# mainboard.net
KiCad netlist of a schematic drawn in EAGLE
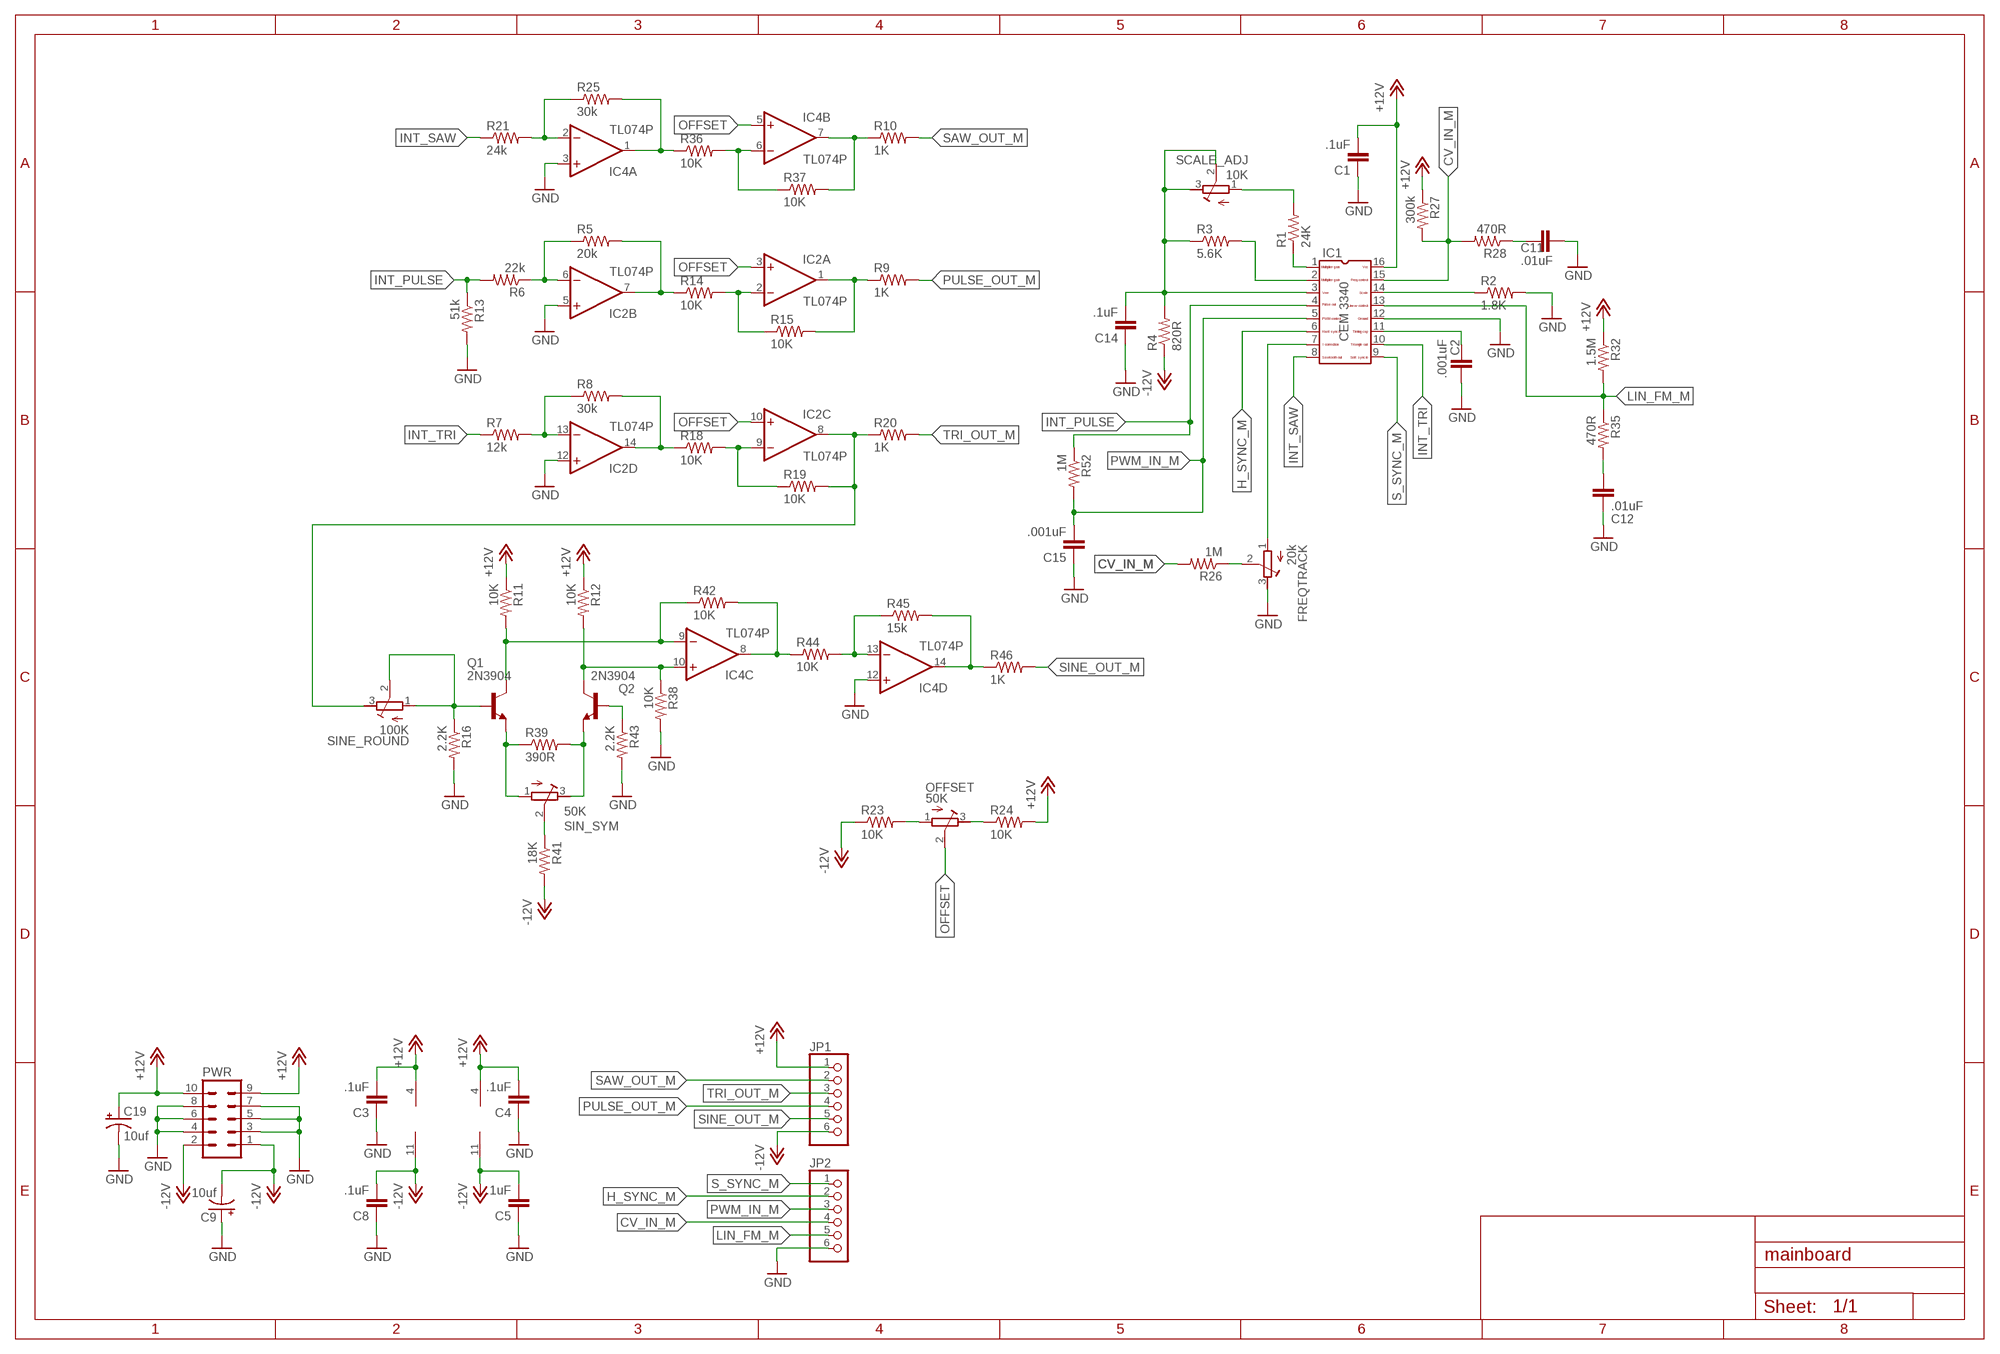
[diagram p0: schematic, sheet 1]

(export (version "E")
  (design (tool "Eeschema 10.0.6"))
  (components
    (comp (ref "C1")
      (value ".1uF")
      (footprint "eagle-import:C050-024X044")
      (libsource (lib "eagle-import") (part "resistor_C-EU050-024X044"))
    )
    (comp (ref "C2")
      (value ".001uF")
      (footprint "eagle-import:C150-054X183")
      (libsource (lib "eagle-import") (part "C-EU150-054X183"))
    )
    (comp (ref "C3")
      (value ".1uF")
      (footprint "eagle-import:C050-024X044")
      (libsource (lib "eagle-import") (part "resistor_C-EU050-024X044"))
    )
    (comp (ref "C4")
      (value ".1uF")
      (footprint "eagle-import:C050-024X044")
      (libsource (lib "eagle-import") (part "resistor_C-EU050-024X044"))
    )
    (comp (ref "C5")
      (value ".1uF")
      (footprint "eagle-import:C050-024X044")
      (libsource (lib "eagle-import") (part "resistor_C-EU050-024X044"))
    )
    (comp (ref "C8")
      (value ".1uF")
      (footprint "eagle-import:C050-024X044")
      (libsource (lib "eagle-import") (part "resistor_C-EU050-024X044"))
    )
    (comp (ref "C9")
      (value "10uf")
      (footprint "eagle-import:E2,5-5")
      (libsource (lib "eagle-import") (part "CPOL-USE2.5-5"))
    )
    (comp (ref "C11")
      (value ".01uF")
      (footprint "eagle-import:C050-024X044")
      (libsource (lib "eagle-import") (part "resistor_C-EU050-024X044"))
    )
    (comp (ref "C12")
      (value ".01uF")
      (footprint "eagle-import:C050-024X044")
      (libsource (lib "eagle-import") (part "resistor_C-EU050-024X044"))
    )
    (comp (ref "C14")
      (value ".1uF")
      (footprint "eagle-import:C050-024X044")
      (libsource (lib "eagle-import") (part "resistor_C-EU050-024X044"))
    )
    (comp (ref "C15")
      (value ".001uF")
      (footprint "eagle-import:C050-024X044")
      (libsource (lib "eagle-import") (part "resistor_C-EU050-024X044"))
    )
    (comp (ref "C19")
      (value "10uf")
      (footprint "eagle-import:E2,5-5")
      (libsource (lib "eagle-import") (part "CPOL-USE2.5-5"))
    )
    (comp (ref "FREQTRACK")
      (value "20k")
      (footprint "eagle-import:RTRIM3296W")
      (libsource (lib "eagle-import") (part "R-TRIMM3296W"))
    )
    (comp (ref "IC1")
      (value "CEM3340")
      (footprint "eagle-import:DIL16")
      (libsource (lib "eagle-import") (part "CEM3340"))
    )
    (comp (ref "IC2")
      (value "TL074P")
      (footprint "eagle-import:DIL14")
      (libsource (lib "eagle-import") (part "TL074P"))
    )
    (comp (ref "IC4")
      (value "TL074P")
      (footprint "eagle-import:DIL14")
      (libsource (lib "eagle-import") (part "linear_262_TL074P"))
    )
    (comp (ref "JP1")
      (value "PINHD-1X6")
      (footprint "eagle-import:1X06")
      (libsource (lib "eagle-import") (part "PINHD-1X6"))
    )
    (comp (ref "JP2")
      (value "PINHD-1X6")
      (footprint "eagle-import:1X06")
      (libsource (lib "eagle-import") (part "PINHD-1X6"))
    )
    (comp (ref "OFFSET")
      (value "50K")
      (footprint "eagle-import:RTRIM3296W")
      (libsource (lib "eagle-import") (part "R-TRIMM3296W"))
    )
    (comp (ref "PWR")
      (value "ML10")
      (footprint "eagle-import:ML10")
      (libsource (lib "eagle-import") (part "ML10"))
    )
    (comp (ref "Q1")
      (value "2N3904")
      (footprint "eagle-import:TO92")
      (libsource (lib "eagle-import") (part "2N3904"))
    )
    (comp (ref "Q2")
      (value "2N3904")
      (footprint "eagle-import:TO92")
      (libsource (lib "eagle-import") (part "2N3904"))
    )
    (comp (ref "R1")
      (value "24K")
      (footprint "eagle-import:0207_7")
      (libsource (lib "eagle-import") (part "R-US_0207/7"))
    )
    (comp (ref "R2")
      (value "1.8K")
      (footprint "eagle-import:0207_7")
      (libsource (lib "eagle-import") (part "R-US_0207/7"))
    )
    (comp (ref "R3")
      (value "5.6K")
      (footprint "eagle-import:0207_7")
      (libsource (lib "eagle-import") (part "R-US_0207/7"))
    )
    (comp (ref "R4")
      (value "820R")
      (footprint "eagle-import:0207_7")
      (libsource (lib "eagle-import") (part "R-US_0207/7"))
    )
    (comp (ref "R5")
      (value "20k")
      (footprint "eagle-import:0207_7")
      (libsource (lib "eagle-import") (part "R-US_0207/7"))
    )
    (comp (ref "R6")
      (value "22k")
      (footprint "eagle-import:0207_7")
      (libsource (lib "eagle-import") (part "R-US_0207/7"))
    )
    (comp (ref "R7")
      (value "12k")
      (footprint "eagle-import:0207_7")
      (libsource (lib "eagle-import") (part "R-US_0207/7"))
    )
    (comp (ref "R8")
      (value "30k")
      (footprint "eagle-import:0207_7")
      (libsource (lib "eagle-import") (part "R-US_0207/7"))
    )
    (comp (ref "R9")
      (value "1K")
      (footprint "eagle-import:0207_7")
      (libsource (lib "eagle-import") (part "R-US_0207/7"))
    )
    (comp (ref "R10")
      (value "1K")
      (footprint "eagle-import:0207_7")
      (libsource (lib "eagle-import") (part "R-US_0207/7"))
    )
    (comp (ref "R11")
      (value "10K")
      (footprint "eagle-import:0207_7")
      (libsource (lib "eagle-import") (part "R-US_0207/7"))
    )
    (comp (ref "R12")
      (value "10K")
      (footprint "eagle-import:0207_7")
      (libsource (lib "eagle-import") (part "R-US_0207/7"))
    )
    (comp (ref "R13")
      (value "51k")
      (footprint "eagle-import:0207_7")
      (libsource (lib "eagle-import") (part "R-US_0207/7"))
    )
    (comp (ref "R14")
      (value "10K")
      (footprint "eagle-import:0207_7")
      (libsource (lib "eagle-import") (part "R-US_0207/7"))
    )
    (comp (ref "R15")
      (value "10K")
      (footprint "eagle-import:0207_7")
      (libsource (lib "eagle-import") (part "R-US_0207/7"))
    )
    (comp (ref "R16")
      (value "2.2K")
      (footprint "eagle-import:0207_7")
      (libsource (lib "eagle-import") (part "R-US_0207/7"))
    )
    (comp (ref "R18")
      (value "10K")
      (footprint "eagle-import:0207_7")
      (libsource (lib "eagle-import") (part "R-US_0207/7"))
    )
    (comp (ref "R19")
      (value "10K")
      (footprint "eagle-import:0207_7")
      (libsource (lib "eagle-import") (part "R-US_0207/7"))
    )
    (comp (ref "R20")
      (value "1K")
      (footprint "eagle-import:0207_7")
      (libsource (lib "eagle-import") (part "R-US_0207/7"))
    )
    (comp (ref "R21")
      (value "24k")
      (footprint "eagle-import:0207_7")
      (libsource (lib "eagle-import") (part "R-US_0207/7"))
    )
    (comp (ref "R23")
      (value "10K")
      (footprint "eagle-import:0207_7")
      (libsource (lib "eagle-import") (part "R-US_0207/7"))
    )
    (comp (ref "R24")
      (value "10K")
      (footprint "eagle-import:0207_7")
      (libsource (lib "eagle-import") (part "resistor_348_R-US_0207/7"))
    )
    (comp (ref "R25")
      (value "30k")
      (footprint "eagle-import:0207_7")
      (libsource (lib "eagle-import") (part "R-US_0207/7"))
    )
    (comp (ref "R26")
      (value "1M")
      (footprint "eagle-import:0207_7")
      (libsource (lib "eagle-import") (part "R-US_0207/7"))
    )
    (comp (ref "R27")
      (value "300k")
      (footprint "eagle-import:0207_7")
      (libsource (lib "eagle-import") (part "R-US_0207/7"))
    )
    (comp (ref "R28")
      (value "470R")
      (footprint "eagle-import:0207_7")
      (libsource (lib "eagle-import") (part "R-US_0207/7"))
    )
    (comp (ref "R32")
      (value "1.5M")
      (footprint "eagle-import:0207_7")
      (libsource (lib "eagle-import") (part "R-US_0207/7"))
    )
    (comp (ref "R35")
      (value "470R")
      (footprint "eagle-import:0207_7")
      (libsource (lib "eagle-import") (part "R-US_0207/7"))
    )
    (comp (ref "R36")
      (value "10K")
      (footprint "eagle-import:0207_7")
      (libsource (lib "eagle-import") (part "R-US_0207/7"))
    )
    (comp (ref "R37")
      (value "10K")
      (footprint "eagle-import:0207_7")
      (libsource (lib "eagle-import") (part "R-US_0207/7"))
    )
    (comp (ref "R38")
      (value "10K")
      (footprint "eagle-import:0207_7")
      (libsource (lib "eagle-import") (part "R-US_0207/7"))
    )
    (comp (ref "R39")
      (value "390R")
      (footprint "eagle-import:0207_7")
      (libsource (lib "eagle-import") (part "R-US_0207/7"))
    )
    (comp (ref "R41")
      (value "18K")
      (footprint "eagle-import:0207_7")
      (libsource (lib "eagle-import") (part "R-US_0207/7"))
    )
    (comp (ref "R42")
      (value "10K")
      (footprint "eagle-import:0207_7")
      (libsource (lib "eagle-import") (part "R-US_0207/7"))
    )
    (comp (ref "R43")
      (value "2.2K")
      (footprint "eagle-import:0207_7")
      (libsource (lib "eagle-import") (part "R-US_0207/7"))
    )
    (comp (ref "R44")
      (value "10K")
      (footprint "eagle-import:0207_7")
      (libsource (lib "eagle-import") (part "R-US_0207/7"))
    )
    (comp (ref "R45")
      (value "15k")
      (footprint "eagle-import:0207_7")
      (libsource (lib "eagle-import") (part "R-US_0207/7"))
    )
    (comp (ref "R46")
      (value "1K")
      (footprint "eagle-import:0207_7")
      (libsource (lib "eagle-import") (part "R-US_0207/7"))
    )
    (comp (ref "R52")
      (value "1M")
      (footprint "eagle-import:0207_7")
      (libsource (lib "eagle-import") (part "R-US_0207/7"))
    )
    (comp (ref "SCALE_ADJ")
      (value "10K")
      (footprint "eagle-import:RTRIM3296W")
      (libsource (lib "eagle-import") (part "R-TRIMM3296W"))
    )
    (comp (ref "SINE_ROUND")
      (value "100K")
      (footprint "eagle-import:RTRIM3296W")
      (libsource (lib "eagle-import") (part "R-TRIMM3296W"))
    )
    (comp (ref "SIN_SYM")
      (value "50K")
      (footprint "eagle-import:RTRIM3296W")
      (libsource (lib "eagle-import") (part "R-TRIMM3296W"))
    )
  )
  (nets
    (net (code "1") (name "+12V") (class "Default")
      (node (ref "C1") (pin "2") (pinfunction "2_2") (pintype "passive"))
      (node (ref "C19") (pin "+") (pinfunction "+_+") (pintype "passive"))
      (node (ref "C3") (pin "2") (pinfunction "2_2") (pintype "passive"))
      (node (ref "C4") (pin "2") (pinfunction "2_2") (pintype "passive"))
      (node (ref "IC1") (pin "16") (pinfunction "16_16") (pintype "power_in"))
      (node (ref "IC2") (pin "4") (pinfunction "V+_4") (pintype "power_in"))
      (node (ref "IC4") (pin "4") (pinfunction "V+_4") (pintype "power_in"))
      (node (ref "JP1") (pin "1") (pinfunction "1_1") (pintype "passive"))
      (node (ref "PWR") (pin "10") (pinfunction "10_10") (pintype "passive"))
      (node (ref "PWR") (pin "9") (pinfunction "9_9") (pintype "passive"))
      (node (ref "R11") (pin "1") (pinfunction "1_1") (pintype "passive"))
      (node (ref "R12") (pin "1") (pinfunction "1_1") (pintype "passive"))
      (node (ref "R24") (pin "2") (pinfunction "2_2") (pintype "passive"))
      (node (ref "R27") (pin "1") (pinfunction "1_1") (pintype "passive"))
      (node (ref "R32") (pin "1") (pinfunction "1_1") (pintype "passive"))
    )
    (net (code "2") (name "-12V") (class "Default")
      (node (ref "C5") (pin "2") (pinfunction "2_2") (pintype "passive"))
      (node (ref "C8") (pin "2") (pinfunction "2_2") (pintype "passive"))
      (node (ref "C9") (pin "-") (pinfunction "-_-") (pintype "passive"))
      (node (ref "IC2") (pin "11") (pinfunction "V-_11") (pintype "power_in"))
      (node (ref "IC4") (pin "11") (pinfunction "V-_11") (pintype "power_in"))
      (node (ref "JP1") (pin "6") (pinfunction "6_6") (pintype "passive"))
      (node (ref "PWR") (pin "1") (pinfunction "1_1") (pintype "passive"))
      (node (ref "PWR") (pin "2") (pinfunction "2_2") (pintype "passive"))
      (node (ref "R23") (pin "1") (pinfunction "1_1") (pintype "passive"))
      (node (ref "R4") (pin "1") (pinfunction "1_1") (pintype "passive"))
      (node (ref "R41") (pin "2") (pinfunction "2_2") (pintype "passive"))
    )
    (net (code "3") (name "CV_IN_M") (class "Default")
      (node (ref "IC1") (pin "15") (pinfunction "15_15") (pintype "input"))
      (node (ref "JP2") (pin "4") (pinfunction "4_4") (pintype "passive"))
      (node (ref "R26") (pin "2") (pinfunction "2_2") (pintype "passive"))
      (node (ref "R27") (pin "2") (pinfunction "2_2") (pintype "passive"))
      (node (ref "R28") (pin "2") (pinfunction "2_2") (pintype "passive"))
    )
    (net (code "4") (name "GND") (class "Default")
      (node (ref "C1") (pin "1") (pinfunction "1_1") (pintype "passive"))
      (node (ref "C11") (pin "1") (pinfunction "1_1") (pintype "passive"))
      (node (ref "C12") (pin "2") (pinfunction "2_2") (pintype "passive"))
      (node (ref "C14") (pin "1") (pinfunction "1_1") (pintype "passive"))
      (node (ref "C15") (pin "1") (pinfunction "1_1") (pintype "passive"))
      (node (ref "C19") (pin "-") (pinfunction "-_-") (pintype "passive"))
      (node (ref "C2") (pin "2") (pinfunction "2_2") (pintype "passive"))
      (node (ref "C3") (pin "1") (pinfunction "1_1") (pintype "passive"))
      (node (ref "C4") (pin "1") (pinfunction "1_1") (pintype "passive"))
      (node (ref "C5") (pin "1") (pinfunction "1_1") (pintype "passive"))
      (node (ref "C8") (pin "1") (pinfunction "1_1") (pintype "passive"))
      (node (ref "C9") (pin "+") (pinfunction "+_+") (pintype "passive"))
      (node (ref "FREQTRACK") (pin "3") (pinfunction "E_3") (pintype "passive"))
      (node (ref "IC1") (pin "12") (pinfunction "12_12") (pintype "power_in"))
      (node (ref "IC2") (pin "12") (pinfunction "+IN_12") (pintype "input"))
      (node (ref "IC2") (pin "5") (pinfunction "+IN_5") (pintype "input"))
      (node (ref "IC4") (pin "12") (pinfunction "+IN_12") (pintype "input"))
      (node (ref "IC4") (pin "3") (pinfunction "+IN_3") (pintype "input"))
      (node (ref "JP2") (pin "6") (pinfunction "6_6") (pintype "passive"))
      (node (ref "PWR") (pin "3") (pinfunction "3_3") (pintype "passive"))
      (node (ref "PWR") (pin "4") (pinfunction "4_4") (pintype "passive"))
      (node (ref "PWR") (pin "5") (pinfunction "5_5") (pintype "passive"))
      (node (ref "PWR") (pin "6") (pinfunction "6_6") (pintype "passive"))
      (node (ref "PWR") (pin "7") (pinfunction "7_7") (pintype "passive"))
      (node (ref "PWR") (pin "8") (pinfunction "8_8") (pintype "passive"))
      (node (ref "R13") (pin "2") (pinfunction "2_2") (pintype "passive"))
      (node (ref "R16") (pin "2") (pinfunction "2_2") (pintype "passive"))
      (node (ref "R2") (pin "2") (pinfunction "2_2") (pintype "passive"))
      (node (ref "R38") (pin "2") (pinfunction "2_2") (pintype "passive"))
      (node (ref "R43") (pin "2") (pinfunction "2_2") (pintype "passive"))
    )
    (net (code "5") (name "H_SYNC_M") (class "Default")
      (node (ref "IC1") (pin "6") (pinfunction "6_6") (pintype "input"))
      (node (ref "JP2") (pin "2") (pinfunction "2_2") (pintype "passive"))
    )
    (net (code "6") (name "INT_PULSE") (class "Default")
      (node (ref "IC1") (pin "4") (pinfunction "4_4") (pintype "output"))
      (node (ref "R13") (pin "1") (pinfunction "1_1") (pintype "passive"))
      (node (ref "R52") (pin "1") (pinfunction "1_1") (pintype "passive"))
      (node (ref "R6") (pin "2") (pinfunction "2_2") (pintype "passive"))
    )
    (net (code "7") (name "INT_SAW") (class "Default")
      (node (ref "IC1") (pin "8") (pinfunction "8_8") (pintype "output"))
      (node (ref "R21") (pin "1") (pinfunction "1_1") (pintype "passive"))
    )
    (net (code "8") (name "INT_TRI") (class "Default")
      (node (ref "IC1") (pin "10") (pinfunction "10_10") (pintype "output"))
      (node (ref "R7") (pin "1") (pinfunction "1_1") (pintype "passive"))
    )
    (net (code "9") (name "LIN_FM_M") (class "Default")
      (node (ref "IC1") (pin "13") (pinfunction "13_13") (pintype "input"))
      (node (ref "JP2") (pin "5") (pinfunction "5_5") (pintype "passive"))
      (node (ref "R32") (pin "2") (pinfunction "2_2") (pintype "passive"))
      (node (ref "R35") (pin "1") (pinfunction "1_1") (pintype "passive"))
    )
    (net (code "10") (name "Net-(C2-Pad1)") (class "Default")
      (node (ref "C2") (pin "1") (pinfunction "1_1") (pintype "passive"))
      (node (ref "IC1") (pin "11") (pinfunction "11_11") (pintype "bidirectional"))
    )
    (net (code "11") (name "Net-(C11-Pad2)") (class "Default")
      (node (ref "C11") (pin "2") (pinfunction "2_2") (pintype "passive"))
      (node (ref "R28") (pin "1") (pinfunction "1_1") (pintype "passive"))
    )
    (net (code "12") (name "Net-(C12-Pad1)") (class "Default")
      (node (ref "C12") (pin "1") (pinfunction "1_1") (pintype "passive"))
      (node (ref "R35") (pin "2") (pinfunction "2_2") (pintype "passive"))
    )
    (net (code "13") (name "Net-(FREQTRACK-A)") (class "Default")
      (node (ref "FREQTRACK") (pin "1") (pinfunction "A_1") (pintype "passive"))
      (node (ref "IC1") (pin "7") (pinfunction "7_7") (pintype "bidirectional"))
    )
    (net (code "14") (name "Net-(FREQTRACK-S)") (class "Default")
      (node (ref "FREQTRACK") (pin "2") (pinfunction "S_2") (pintype "passive"))
      (node (ref "R26") (pin "1") (pinfunction "1_1") (pintype "passive"))
    )
    (net (code "15") (name "Net-(IC1-Pad1)") (class "Default")
      (node (ref "IC1") (pin "1") (pinfunction "1_1") (pintype "bidirectional"))
      (node (ref "R1") (pin "1") (pinfunction "1_1") (pintype "passive"))
    )
    (net (code "16") (name "Net-(IC1-Pad2)") (class "Default")
      (node (ref "IC1") (pin "2") (pinfunction "2_2") (pintype "bidirectional"))
      (node (ref "R3") (pin "2") (pinfunction "2_2") (pintype "passive"))
    )
    (net (code "17") (name "Net-(IC1-Pad14)") (class "Default")
      (node (ref "IC1") (pin "14") (pinfunction "14_14") (pintype "input"))
      (node (ref "R2") (pin "1") (pinfunction "1_1") (pintype "passive"))
    )
    (net (code "18") (name "Net-(IC2A--IN)") (class "Default")
      (node (ref "IC2") (pin "2") (pinfunction "-IN_2") (pintype "input"))
      (node (ref "R14") (pin "2") (pinfunction "2_2") (pintype "passive"))
      (node (ref "R15") (pin "1") (pinfunction "1_1") (pintype "passive"))
    )
    (net (code "19") (name "Net-(IC2A-OUT)") (class "Default")
      (node (ref "IC2") (pin "1") (pinfunction "OUT_1") (pintype "output"))
      (node (ref "R15") (pin "2") (pinfunction "2_2") (pintype "passive"))
      (node (ref "R9") (pin "1") (pinfunction "1_1") (pintype "passive"))
    )
    (net (code "20") (name "Net-(IC2B--IN)") (class "Default")
      (node (ref "IC2") (pin "6") (pinfunction "-IN_6") (pintype "input"))
      (node (ref "R5") (pin "1") (pinfunction "1_1") (pintype "passive"))
      (node (ref "R6") (pin "1") (pinfunction "1_1") (pintype "passive"))
    )
    (net (code "21") (name "Net-(IC2B-OUT)") (class "Default")
      (node (ref "IC2") (pin "7") (pinfunction "OUT_7") (pintype "output"))
      (node (ref "R14") (pin "1") (pinfunction "1_1") (pintype "passive"))
      (node (ref "R5") (pin "2") (pinfunction "2_2") (pintype "passive"))
    )
    (net (code "22") (name "Net-(IC2C--IN)") (class "Default")
      (node (ref "IC2") (pin "9") (pinfunction "-IN_9") (pintype "input"))
      (node (ref "R18") (pin "2") (pinfunction "2_2") (pintype "passive"))
      (node (ref "R19") (pin "1") (pinfunction "1_1") (pintype "passive"))
    )
    (net (code "23") (name "Net-(IC2C-OUT)") (class "Default")
      (node (ref "IC2") (pin "8") (pinfunction "OUT_8") (pintype "output"))
      (node (ref "R19") (pin "2") (pinfunction "2_2") (pintype "passive"))
      (node (ref "R20") (pin "1") (pinfunction "1_1") (pintype "passive"))
      (node (ref "SINE_ROUND") (pin "3") (pinfunction "E_3") (pintype "passive"))
    )
    (net (code "24") (name "Net-(IC2D--IN)") (class "Default")
      (node (ref "IC2") (pin "13") (pinfunction "-IN_13") (pintype "input"))
      (node (ref "R7") (pin "2") (pinfunction "2_2") (pintype "passive"))
      (node (ref "R8") (pin "1") (pinfunction "1_1") (pintype "passive"))
    )
    (net (code "25") (name "Net-(IC2D-OUT)") (class "Default")
      (node (ref "IC2") (pin "14") (pinfunction "OUT_14") (pintype "output"))
      (node (ref "R18") (pin "1") (pinfunction "1_1") (pintype "passive"))
      (node (ref "R8") (pin "2") (pinfunction "2_2") (pintype "passive"))
    )
    (net (code "26") (name "Net-(IC4A--IN)") (class "Default")
      (node (ref "IC4") (pin "2") (pinfunction "-IN_2") (pintype "input"))
      (node (ref "R21") (pin "2") (pinfunction "2_2") (pintype "passive"))
      (node (ref "R25") (pin "1") (pinfunction "1_1") (pintype "passive"))
    )
    (net (code "27") (name "Net-(IC4A-OUT)") (class "Default")
      (node (ref "IC4") (pin "1") (pinfunction "OUT_1") (pintype "output"))
      (node (ref "R25") (pin "2") (pinfunction "2_2") (pintype "passive"))
      (node (ref "R36") (pin "1") (pinfunction "1_1") (pintype "passive"))
    )
    (net (code "28") (name "Net-(IC4B--IN)") (class "Default")
      (node (ref "IC4") (pin "6") (pinfunction "-IN_6") (pintype "input"))
      (node (ref "R36") (pin "2") (pinfunction "2_2") (pintype "passive"))
      (node (ref "R37") (pin "1") (pinfunction "1_1") (pintype "passive"))
    )
    (net (code "29") (name "Net-(IC4B-OUT)") (class "Default")
      (node (ref "IC4") (pin "7") (pinfunction "OUT_7") (pintype "output"))
      (node (ref "R10") (pin "1") (pinfunction "1_1") (pintype "passive"))
      (node (ref "R37") (pin "2") (pinfunction "2_2") (pintype "passive"))
    )
    (net (code "30") (name "Net-(IC4C-+IN)") (class "Default")
      (node (ref "IC4") (pin "10") (pinfunction "+IN_10") (pintype "input"))
      (node (ref "Q2") (pin "1") (pinfunction "C_1") (pintype "passive"))
      (node (ref "R12") (pin "2") (pinfunction "2_2") (pintype "passive"))
      (node (ref "R38") (pin "1") (pinfunction "1_1") (pintype "passive"))
    )
    (net (code "31") (name "Net-(IC4C--IN)") (class "Default")
      (node (ref "IC4") (pin "9") (pinfunction "-IN_9") (pintype "input"))
      (node (ref "Q1") (pin "1") (pinfunction "C_1") (pintype "passive"))
      (node (ref "R11") (pin "2") (pinfunction "2_2") (pintype "passive"))
      (node (ref "R42") (pin "1") (pinfunction "1_1") (pintype "passive"))
    )
    (net (code "32") (name "Net-(IC4C-OUT)") (class "Default")
      (node (ref "IC4") (pin "8") (pinfunction "OUT_8") (pintype "output"))
      (node (ref "R42") (pin "2") (pinfunction "2_2") (pintype "passive"))
      (node (ref "R44") (pin "1") (pinfunction "1_1") (pintype "passive"))
    )
    (net (code "33") (name "Net-(IC4D--IN)") (class "Default")
      (node (ref "IC4") (pin "13") (pinfunction "-IN_13") (pintype "input"))
      (node (ref "R44") (pin "2") (pinfunction "2_2") (pintype "passive"))
      (node (ref "R45") (pin "1") (pinfunction "1_1") (pintype "passive"))
    )
    (net (code "34") (name "Net-(IC4D-OUT)") (class "Default")
      (node (ref "IC4") (pin "14") (pinfunction "OUT_14") (pintype "output"))
      (node (ref "R45") (pin "2") (pinfunction "2_2") (pintype "passive"))
      (node (ref "R46") (pin "1") (pinfunction "1_1") (pintype "passive"))
    )
    (net (code "35") (name "Net-(OFFSET-A)") (class "Default")
      (node (ref "OFFSET") (pin "1") (pinfunction "A_1") (pintype "passive"))
      (node (ref "R23") (pin "2") (pinfunction "2_2") (pintype "passive"))
    )
    (net (code "36") (name "Net-(OFFSET-E)") (class "Default")
      (node (ref "OFFSET") (pin "3") (pinfunction "E_3") (pintype "passive"))
      (node (ref "R24") (pin "1") (pinfunction "1_1") (pintype "passive"))
    )
    (net (code "37") (name "Net-(Q1-B)") (class "Default")
      (node (ref "Q1") (pin "2") (pinfunction "B_2") (pintype "passive"))
      (node (ref "R16") (pin "1") (pinfunction "1_1") (pintype "passive"))
      (node (ref "SINE_ROUND") (pin "1") (pinfunction "A_1") (pintype "passive"))
      (node (ref "SINE_ROUND") (pin "2") (pinfunction "S_2") (pintype "passive"))
    )
    (net (code "38") (name "Net-(Q1-E)") (class "Default")
      (node (ref "Q1") (pin "3") (pinfunction "E_3") (pintype "passive"))
      (node (ref "R39") (pin "1") (pinfunction "1_1") (pintype "passive"))
      (node (ref "SIN_SYM") (pin "1") (pinfunction "A_1") (pintype "passive"))
    )
    (net (code "39") (name "Net-(Q2-B)") (class "Default")
      (node (ref "Q2") (pin "2") (pinfunction "B_2") (pintype "passive"))
      (node (ref "R43") (pin "1") (pinfunction "1_1") (pintype "passive"))
    )
    (net (code "40") (name "Net-(Q2-E)") (class "Default")
      (node (ref "Q2") (pin "3") (pinfunction "E_3") (pintype "passive"))
      (node (ref "R39") (pin "2") (pinfunction "2_2") (pintype "passive"))
      (node (ref "SIN_SYM") (pin "3") (pinfunction "E_3") (pintype "passive"))
    )
    (net (code "41") (name "Net-(SCALE_ADJ-A)") (class "Default")
      (node (ref "R1") (pin "2") (pinfunction "2_2") (pintype "passive"))
      (node (ref "SCALE_ADJ") (pin "1") (pinfunction "A_1") (pintype "passive"))
    )
    (net (code "42") (name "Net-(SCALE_ADJ-E)") (class "Default")
      (node (ref "C14") (pin "2") (pinfunction "2_2") (pintype "passive"))
      (node (ref "IC1") (pin "3") (pinfunction "3_3") (pintype "power_in"))
      (node (ref "R3") (pin "1") (pinfunction "1_1") (pintype "passive"))
      (node (ref "R4") (pin "2") (pinfunction "2_2") (pintype "passive"))
      (node (ref "SCALE_ADJ") (pin "2") (pinfunction "S_2") (pintype "passive"))
      (node (ref "SCALE_ADJ") (pin "3") (pinfunction "E_3") (pintype "passive"))
    )
    (net (code "43") (name "Net-(SIN_SYM-S)") (class "Default")
      (node (ref "R41") (pin "1") (pinfunction "1_1") (pintype "passive"))
      (node (ref "SIN_SYM") (pin "2") (pinfunction "S_2") (pintype "passive"))
    )
    (net (code "44") (name "OFFSET") (class "Default")
      (node (ref "IC2") (pin "10") (pinfunction "+IN_10") (pintype "input"))
      (node (ref "IC2") (pin "3") (pinfunction "+IN_3") (pintype "input"))
      (node (ref "IC4") (pin "5") (pinfunction "+IN_5") (pintype "input"))
      (node (ref "OFFSET") (pin "2") (pinfunction "S_2") (pintype "passive"))
    )
    (net (code "45") (name "PULSE_OUT_M") (class "Default")
      (node (ref "JP1") (pin "4") (pinfunction "4_4") (pintype "passive"))
      (node (ref "R9") (pin "2") (pinfunction "2_2") (pintype "passive"))
    )
    (net (code "46") (name "PWM_IN_M") (class "Default")
      (node (ref "C15") (pin "2") (pinfunction "2_2") (pintype "passive"))
      (node (ref "IC1") (pin "5") (pinfunction "5_5") (pintype "input"))
      (node (ref "JP2") (pin "3") (pinfunction "3_3") (pintype "passive"))
      (node (ref "R52") (pin "2") (pinfunction "2_2") (pintype "passive"))
    )
    (net (code "47") (name "SAW_OUT_M") (class "Default")
      (node (ref "JP1") (pin "2") (pinfunction "2_2") (pintype "passive"))
      (node (ref "R10") (pin "2") (pinfunction "2_2") (pintype "passive"))
    )
    (net (code "48") (name "SINE_OUT_M") (class "Default")
      (node (ref "JP1") (pin "5") (pinfunction "5_5") (pintype "passive"))
      (node (ref "R46") (pin "2") (pinfunction "2_2") (pintype "passive"))
    )
    (net (code "49") (name "S_SYNC_M") (class "Default")
      (node (ref "IC1") (pin "9") (pinfunction "9_9") (pintype "input"))
      (node (ref "JP2") (pin "1") (pinfunction "1_1") (pintype "passive"))
    )
    (net (code "50") (name "TRI_OUT_M") (class "Default")
      (node (ref "JP1") (pin "3") (pinfunction "3_3") (pintype "passive"))
      (node (ref "R20") (pin "2") (pinfunction "2_2") (pintype "passive"))
    )
  )
)
